# 05_-_DISP_DRIVERS.net
KiCad netlist of a schematic drawn in Altium Designer
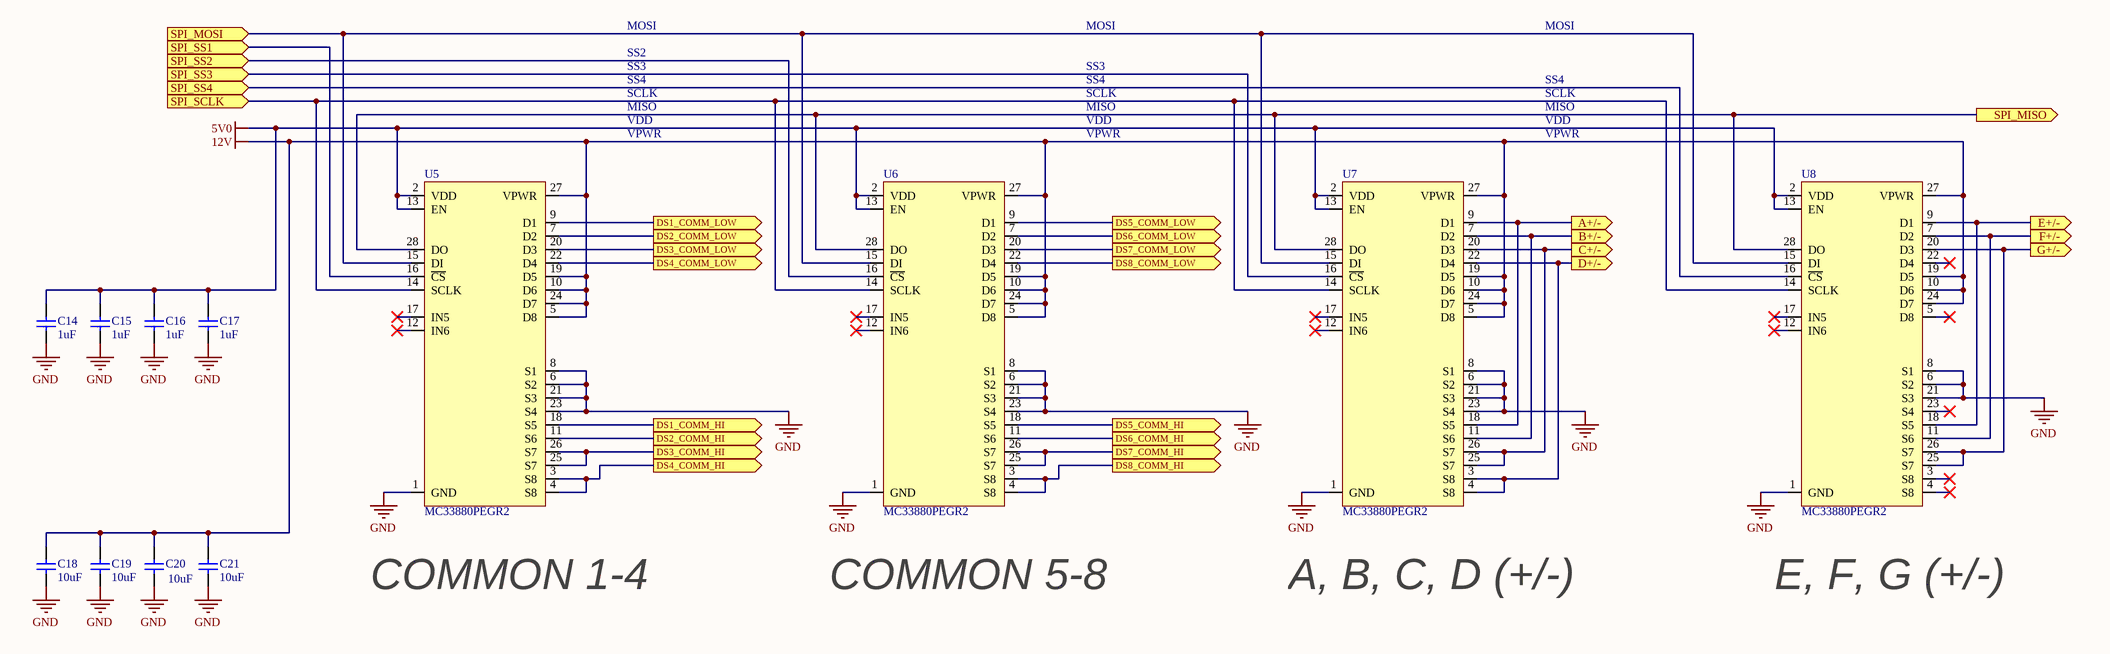
[diagram p0: [05] - DISP DRIVERS.SchDoc]

(export (version "E")
  (design (tool "Eeschema 10.0.6"))
  (components
    (comp (ref "C14")
      (value "1uF")
      (footprint "INCH 0603 - METRIC 1608 - H090")
      (description "CAP CER 1UF 16V X7R 0603")
      (fields
        (field (name "MANUFACTURER") "Samsung")
        (field (name "MANUFACTURER PART NUMBER") "CL10B105KO8NNNC")
      )
      (libsource (lib "Capacitors") (part "CL10B105KO8NNNC"))
    )
    (comp (ref "C15")
      (value "1uF")
      (footprint "INCH 0603 - METRIC 1608 - H090")
      (description "CAP CER 1UF 16V X7R 0603")
      (fields
        (field (name "MANUFACTURER") "Samsung")
        (field (name "MANUFACTURER PART NUMBER") "CL10B105KO8NNNC")
      )
      (libsource (lib "Capacitors") (part "CL10B105KO8NNNC"))
    )
    (comp (ref "C16")
      (value "1uF")
      (footprint "INCH 0603 - METRIC 1608 - H090")
      (description "CAP CER 1UF 16V X7R 0603")
      (fields
        (field (name "MANUFACTURER") "Samsung")
        (field (name "MANUFACTURER PART NUMBER") "CL10B105KO8NNNC")
      )
      (libsource (lib "Capacitors") (part "CL10B105KO8NNNC"))
    )
    (comp (ref "C17")
      (value "1uF")
      (footprint "INCH 0603 - METRIC 1608 - H090")
      (description "CAP CER 1UF 16V X7R 0603")
      (fields
        (field (name "MANUFACTURER") "Samsung")
        (field (name "MANUFACTURER PART NUMBER") "CL10B105KO8NNNC")
      )
      (libsource (lib "Capacitors") (part "CL10B105KO8NNNC"))
    )
    (comp (ref "C18")
      (value "10uF")
      (footprint "INCH 0805 - METRIC 2012 - H140")
      (description "CAP CER 10UF 25V X5R 0805")
      (fields
        (field (name "MANUFACTURER") "Murata")
        (field (name "MANUFACTURER PART NUMBER") "GRM21BR61E106MA73L")
      )
      (libsource (lib "Capacitors") (part "GRM21BR61E106MA73L"))
    )
    (comp (ref "C19")
      (value "10uF")
      (footprint "INCH 0805 - METRIC 2012 - H140")
      (description "CAP CER 10UF 25V X5R 0805")
      (fields
        (field (name "MANUFACTURER") "Murata")
        (field (name "MANUFACTURER PART NUMBER") "GRM21BR61E106MA73L")
      )
      (libsource (lib "Capacitors") (part "GRM21BR61E106MA73L"))
    )
    (comp (ref "C20")
      (value "10uF")
      (footprint "INCH 0805 - METRIC 2012 - H140")
      (description "CAP CER 10UF 25V X5R 0805")
      (fields
        (field (name "MANUFACTURER") "Murata")
        (field (name "MANUFACTURER PART NUMBER") "GRM21BR61E106MA73L")
      )
      (libsource (lib "Capacitors") (part "GRM21BR61E106MA73L"))
    )
    (comp (ref "C21")
      (value "10uF")
      (footprint "INCH 0805 - METRIC 2012 - H140")
      (description "CAP CER 10UF 25V X5R 0805")
      (fields
        (field (name "MANUFACTURER") "Murata")
        (field (name "MANUFACTURER PART NUMBER") "GRM21BR61E106MA73L")
      )
      (libsource (lib "Capacitors") (part "GRM21BR61E106MA73L"))
    )
    (comp (ref "U5")
      (value "MC33880PEGR2")
      (footprint "SOIC28P127_1792X1030X265L65X42")
      (description "IC SRL SWITCH OCT W/SPI 28SOIC")
      (fields (field (name "MANUFACTURER") "NXP Semiconductors"))
      (libsource (lib "ICs - Drivers") (part "MC33880PEGR2"))
    )
    (comp (ref "U6")
      (value "MC33880PEGR2")
      (footprint "SOIC28P127_1792X1030X265L65X42")
      (description "IC SRL SWITCH OCT W/SPI 28SOIC")
      (fields (field (name "MANUFACTURER") "NXP Semiconductors"))
      (libsource (lib "ICs - Drivers") (part "MC33880PEGR2"))
    )
    (comp (ref "U7")
      (value "MC33880PEGR2")
      (footprint "SOIC28P127_1792X1030X265L65X42")
      (description "IC SRL SWITCH OCT W/SPI 28SOIC")
      (fields (field (name "MANUFACTURER") "NXP Semiconductors"))
      (libsource (lib "ICs - Drivers") (part "MC33880PEGR2"))
    )
    (comp (ref "U8")
      (value "MC33880PEGR2")
      (footprint "SOIC28P127_1792X1030X265L65X42")
      (description "IC SRL SWITCH OCT W/SPI 28SOIC")
      (fields (field (name "MANUFACTURER") "NXP Semiconductors"))
      (libsource (lib "ICs - Drivers") (part "MC33880PEGR2"))
    )
  )
  (nets
    (net (code "1") (name "/A+{slash}-") (class "Default")
      (node (ref "U7") (pin "18") (pinfunction "S5_18") (pintype "passive"))
      (node (ref "U7") (pin "9") (pinfunction "D1_9") (pintype "passive"))
    )
    (net (code "2") (name "/B+{slash}-") (class "Default")
      (node (ref "U7") (pin "11") (pinfunction "S6_11") (pintype "passive"))
      (node (ref "U7") (pin "7") (pinfunction "D2_7") (pintype "passive"))
    )
    (net (code "3") (name "/C+{slash}-") (class "Default")
      (node (ref "U7") (pin "20") (pinfunction "D3_20") (pintype "passive"))
      (node (ref "U7") (pin "25") (pinfunction "S7_25") (pintype "passive"))
      (node (ref "U7") (pin "26") (pinfunction "S7_26") (pintype "passive"))
    )
    (net (code "4") (name "/D+{slash}-") (class "Default")
      (node (ref "U7") (pin "22") (pinfunction "D4_22") (pintype "passive"))
      (node (ref "U7") (pin "3") (pinfunction "S8_3") (pintype "passive"))
      (node (ref "U7") (pin "4") (pinfunction "S8_4") (pintype "passive"))
    )
    (net (code "5") (name "/DS1_COMM_HI") (class "Default")
      (node (ref "U5") (pin "18") (pinfunction "S5_18") (pintype "passive"))
    )
    (net (code "6") (name "/DS1_COMM_LOW") (class "Default")
      (node (ref "U5") (pin "9") (pinfunction "D1_9") (pintype "passive"))
    )
    (net (code "7") (name "/DS2_COMM_HI") (class "Default")
      (node (ref "U5") (pin "11") (pinfunction "S6_11") (pintype "passive"))
    )
    (net (code "8") (name "/DS2_COMM_LOW") (class "Default")
      (node (ref "U5") (pin "7") (pinfunction "D2_7") (pintype "passive"))
    )
    (net (code "9") (name "/DS3_COMM_HI") (class "Default")
      (node (ref "U5") (pin "25") (pinfunction "S7_25") (pintype "passive"))
      (node (ref "U5") (pin "26") (pinfunction "S7_26") (pintype "passive"))
    )
    (net (code "10") (name "/DS3_COMM_LOW") (class "Default")
      (node (ref "U5") (pin "20") (pinfunction "D3_20") (pintype "passive"))
    )
    (net (code "11") (name "/DS4_COMM_HI") (class "Default")
      (node (ref "U5") (pin "3") (pinfunction "S8_3") (pintype "passive"))
      (node (ref "U5") (pin "4") (pinfunction "S8_4") (pintype "passive"))
    )
    (net (code "12") (name "/DS4_COMM_LOW") (class "Default")
      (node (ref "U5") (pin "22") (pinfunction "D4_22") (pintype "passive"))
    )
    (net (code "13") (name "/DS5_COMM_HI") (class "Default")
      (node (ref "U6") (pin "18") (pinfunction "S5_18") (pintype "passive"))
    )
    (net (code "14") (name "/DS5_COMM_LOW") (class "Default")
      (node (ref "U6") (pin "9") (pinfunction "D1_9") (pintype "passive"))
    )
    (net (code "15") (name "/DS6_COMM_HI") (class "Default")
      (node (ref "U6") (pin "11") (pinfunction "S6_11") (pintype "passive"))
    )
    (net (code "16") (name "/DS6_COMM_LOW") (class "Default")
      (node (ref "U6") (pin "7") (pinfunction "D2_7") (pintype "passive"))
    )
    (net (code "17") (name "/DS7_COMM_HI") (class "Default")
      (node (ref "U6") (pin "25") (pinfunction "S7_25") (pintype "passive"))
      (node (ref "U6") (pin "26") (pinfunction "S7_26") (pintype "passive"))
    )
    (net (code "18") (name "/DS7_COMM_LOW") (class "Default")
      (node (ref "U6") (pin "20") (pinfunction "D3_20") (pintype "passive"))
    )
    (net (code "19") (name "/DS8_COMM_HI") (class "Default")
      (node (ref "U6") (pin "3") (pinfunction "S8_3") (pintype "passive"))
      (node (ref "U6") (pin "4") (pinfunction "S8_4") (pintype "passive"))
    )
    (net (code "20") (name "/DS8_COMM_LOW") (class "Default")
      (node (ref "U6") (pin "22") (pinfunction "D4_22") (pintype "passive"))
    )
    (net (code "21") (name "/E+{slash}-") (class "Default")
      (node (ref "U8") (pin "18") (pinfunction "S5_18") (pintype "passive"))
      (node (ref "U8") (pin "9") (pinfunction "D1_9") (pintype "passive"))
    )
    (net (code "22") (name "/F+{slash}-") (class "Default")
      (node (ref "U8") (pin "11") (pinfunction "S6_11") (pintype "passive"))
      (node (ref "U8") (pin "7") (pinfunction "D2_7") (pintype "passive"))
    )
    (net (code "23") (name "/G+{slash}-") (class "Default")
      (node (ref "U8") (pin "20") (pinfunction "D3_20") (pintype "passive"))
      (node (ref "U8") (pin "25") (pinfunction "S7_25") (pintype "passive"))
      (node (ref "U8") (pin "26") (pinfunction "S7_26") (pintype "passive"))
    )
    (net (code "24") (name "/SPI_MISO") (class "Default")
      (node (ref "U5") (pin "28") (pinfunction "DO_28") (pintype "passive"))
      (node (ref "U6") (pin "28") (pinfunction "DO_28") (pintype "passive"))
      (node (ref "U7") (pin "28") (pinfunction "DO_28") (pintype "passive"))
      (node (ref "U8") (pin "28") (pinfunction "DO_28") (pintype "passive"))
    )
    (net (code "25") (name "/SPI_MOSI") (class "Default")
      (node (ref "U5") (pin "15") (pinfunction "DI_15") (pintype "passive"))
      (node (ref "U6") (pin "15") (pinfunction "DI_15") (pintype "passive"))
      (node (ref "U7") (pin "15") (pinfunction "DI_15") (pintype "passive"))
      (node (ref "U8") (pin "15") (pinfunction "DI_15") (pintype "passive"))
    )
    (net (code "26") (name "/SPI_SCLK") (class "Default")
      (node (ref "U5") (pin "14") (pinfunction "SCLK_14") (pintype "passive"))
      (node (ref "U6") (pin "14") (pinfunction "SCLK_14") (pintype "passive"))
      (node (ref "U7") (pin "14") (pinfunction "SCLK_14") (pintype "passive"))
      (node (ref "U8") (pin "14") (pinfunction "SCLK_14") (pintype "passive"))
    )
    (net (code "27") (name "/SPI_SS1") (class "Default")
      (node (ref "U5") (pin "16") (pinfunction "~{CS}_16") (pintype "passive"))
    )
    (net (code "28") (name "/SPI_SS2") (class "Default")
      (node (ref "U6") (pin "16") (pinfunction "~{CS}_16") (pintype "passive"))
    )
    (net (code "29") (name "/SPI_SS3") (class "Default")
      (node (ref "U7") (pin "16") (pinfunction "~{CS}_16") (pintype "passive"))
    )
    (net (code "30") (name "/SPI_SS4") (class "Default")
      (node (ref "U8") (pin "16") (pinfunction "~{CS}_16") (pintype "passive"))
    )
    (net (code "31") (name "5V0") (class "Default")
      (node (ref "C14") (pin "1") (pintype "passive"))
      (node (ref "C15") (pin "1") (pintype "passive"))
      (node (ref "C16") (pin "1") (pintype "passive"))
      (node (ref "C17") (pin "1") (pintype "passive"))
      (node (ref "U5") (pin "13") (pinfunction "EN_13") (pintype "passive"))
      (node (ref "U5") (pin "2") (pinfunction "VDD_2") (pintype "passive"))
      (node (ref "U6") (pin "13") (pinfunction "EN_13") (pintype "passive"))
      (node (ref "U6") (pin "2") (pinfunction "VDD_2") (pintype "passive"))
      (node (ref "U7") (pin "13") (pinfunction "EN_13") (pintype "passive"))
      (node (ref "U7") (pin "2") (pinfunction "VDD_2") (pintype "passive"))
      (node (ref "U8") (pin "13") (pinfunction "EN_13") (pintype "passive"))
      (node (ref "U8") (pin "2") (pinfunction "VDD_2") (pintype "passive"))
    )
    (net (code "32") (name "12V") (class "Default")
      (node (ref "C18") (pin "1") (pintype "passive"))
      (node (ref "C19") (pin "1") (pintype "passive"))
      (node (ref "C20") (pin "1") (pintype "passive"))
      (node (ref "C21") (pin "1") (pintype "passive"))
      (node (ref "U5") (pin "10") (pinfunction "D6_10") (pintype "passive"))
      (node (ref "U5") (pin "19") (pinfunction "D5_19") (pintype "passive"))
      (node (ref "U5") (pin "24") (pinfunction "D7_24") (pintype "passive"))
      (node (ref "U5") (pin "27") (pinfunction "VPWR_27") (pintype "passive"))
      (node (ref "U5") (pin "5") (pinfunction "D8_5") (pintype "passive"))
      (node (ref "U6") (pin "10") (pinfunction "D6_10") (pintype "passive"))
      (node (ref "U6") (pin "19") (pinfunction "D5_19") (pintype "passive"))
      (node (ref "U6") (pin "24") (pinfunction "D7_24") (pintype "passive"))
      (node (ref "U6") (pin "27") (pinfunction "VPWR_27") (pintype "passive"))
      (node (ref "U6") (pin "5") (pinfunction "D8_5") (pintype "passive"))
      (node (ref "U7") (pin "10") (pinfunction "D6_10") (pintype "passive"))
      (node (ref "U7") (pin "19") (pinfunction "D5_19") (pintype "passive"))
      (node (ref "U7") (pin "24") (pinfunction "D7_24") (pintype "passive"))
      (node (ref "U7") (pin "27") (pinfunction "VPWR_27") (pintype "passive"))
      (node (ref "U7") (pin "5") (pinfunction "D8_5") (pintype "passive"))
      (node (ref "U8") (pin "10") (pinfunction "D6_10") (pintype "passive"))
      (node (ref "U8") (pin "19") (pinfunction "D5_19") (pintype "passive"))
      (node (ref "U8") (pin "24") (pinfunction "D7_24") (pintype "passive"))
      (node (ref "U8") (pin "27") (pinfunction "VPWR_27") (pintype "passive"))
    )
    (net (code "33") (name "GND") (class "Default")
      (node (ref "C14") (pin "2") (pintype "passive"))
      (node (ref "C15") (pin "2") (pintype "passive"))
      (node (ref "C16") (pin "2") (pintype "passive"))
      (node (ref "C17") (pin "2") (pintype "passive"))
      (node (ref "C18") (pin "2") (pintype "passive"))
      (node (ref "C19") (pin "2") (pintype "passive"))
      (node (ref "C20") (pin "2") (pintype "passive"))
      (node (ref "C21") (pin "2") (pintype "passive"))
      (node (ref "U5") (pin "1") (pinfunction "GND_1") (pintype "passive"))
      (node (ref "U5") (pin "21") (pinfunction "S3_21") (pintype "passive"))
      (node (ref "U5") (pin "23") (pinfunction "S4_23") (pintype "passive"))
      (node (ref "U5") (pin "6") (pinfunction "S2_6") (pintype "passive"))
      (node (ref "U5") (pin "8") (pinfunction "S1_8") (pintype "passive"))
      (node (ref "U6") (pin "1") (pinfunction "GND_1") (pintype "passive"))
      (node (ref "U6") (pin "21") (pinfunction "S3_21") (pintype "passive"))
      (node (ref "U6") (pin "23") (pinfunction "S4_23") (pintype "passive"))
      (node (ref "U6") (pin "6") (pinfunction "S2_6") (pintype "passive"))
      (node (ref "U6") (pin "8") (pinfunction "S1_8") (pintype "passive"))
      (node (ref "U7") (pin "1") (pinfunction "GND_1") (pintype "passive"))
      (node (ref "U7") (pin "21") (pinfunction "S3_21") (pintype "passive"))
      (node (ref "U7") (pin "23") (pinfunction "S4_23") (pintype "passive"))
      (node (ref "U7") (pin "6") (pinfunction "S2_6") (pintype "passive"))
      (node (ref "U7") (pin "8") (pinfunction "S1_8") (pintype "passive"))
      (node (ref "U8") (pin "1") (pinfunction "GND_1") (pintype "passive"))
      (node (ref "U8") (pin "21") (pinfunction "S3_21") (pintype "passive"))
      (node (ref "U8") (pin "6") (pinfunction "S2_6") (pintype "passive"))
      (node (ref "U8") (pin "8") (pinfunction "S1_8") (pintype "passive"))
    )
    (net (code "34") (name "unconnected-(U5-IN5-Pad17)") (class "Default")
      (node (ref "U5") (pin "17") (pinfunction "IN5_17") (pintype "passive+no_connect"))
    )
    (net (code "35") (name "unconnected-(U5-IN6-Pad12)") (class "Default")
      (node (ref "U5") (pin "12") (pinfunction "IN6_12") (pintype "passive+no_connect"))
    )
    (net (code "36") (name "unconnected-(U6-IN5-Pad17)") (class "Default")
      (node (ref "U6") (pin "17") (pinfunction "IN5_17") (pintype "passive+no_connect"))
    )
    (net (code "37") (name "unconnected-(U6-IN6-Pad12)") (class "Default")
      (node (ref "U6") (pin "12") (pinfunction "IN6_12") (pintype "passive+no_connect"))
    )
    (net (code "38") (name "unconnected-(U7-IN5-Pad17)") (class "Default")
      (node (ref "U7") (pin "17") (pinfunction "IN5_17") (pintype "passive+no_connect"))
    )
    (net (code "39") (name "unconnected-(U7-IN6-Pad12)") (class "Default")
      (node (ref "U7") (pin "12") (pinfunction "IN6_12") (pintype "passive+no_connect"))
    )
    (net (code "40") (name "unconnected-(U8-D4-Pad22)") (class "Default")
      (node (ref "U8") (pin "22") (pinfunction "D4_22") (pintype "passive+no_connect"))
    )
    (net (code "41") (name "unconnected-(U8-D8-Pad5)") (class "Default")
      (node (ref "U8") (pin "5") (pinfunction "D8_5") (pintype "passive+no_connect"))
    )
    (net (code "42") (name "unconnected-(U8-IN5-Pad17)") (class "Default")
      (node (ref "U8") (pin "17") (pinfunction "IN5_17") (pintype "passive+no_connect"))
    )
    (net (code "43") (name "unconnected-(U8-IN6-Pad12)") (class "Default")
      (node (ref "U8") (pin "12") (pinfunction "IN6_12") (pintype "passive+no_connect"))
    )
    (net (code "44") (name "unconnected-(U8-S4-Pad23)") (class "Default")
      (node (ref "U8") (pin "23") (pinfunction "S4_23") (pintype "passive+no_connect"))
    )
    (net (code "45") (name "unconnected-(U8-S8-Pad3)") (class "Default")
      (node (ref "U8") (pin "3") (pinfunction "S8_3") (pintype "passive+no_connect"))
    )
    (net (code "46") (name "unconnected-(U8-S8-Pad4)") (class "Default")
      (node (ref "U8") (pin "4") (pinfunction "S8_4") (pintype "passive+no_connect"))
    )
  )
)
